# Board_Schamatic08.net
KiCad netlist of a schematic drawn in EAGLE
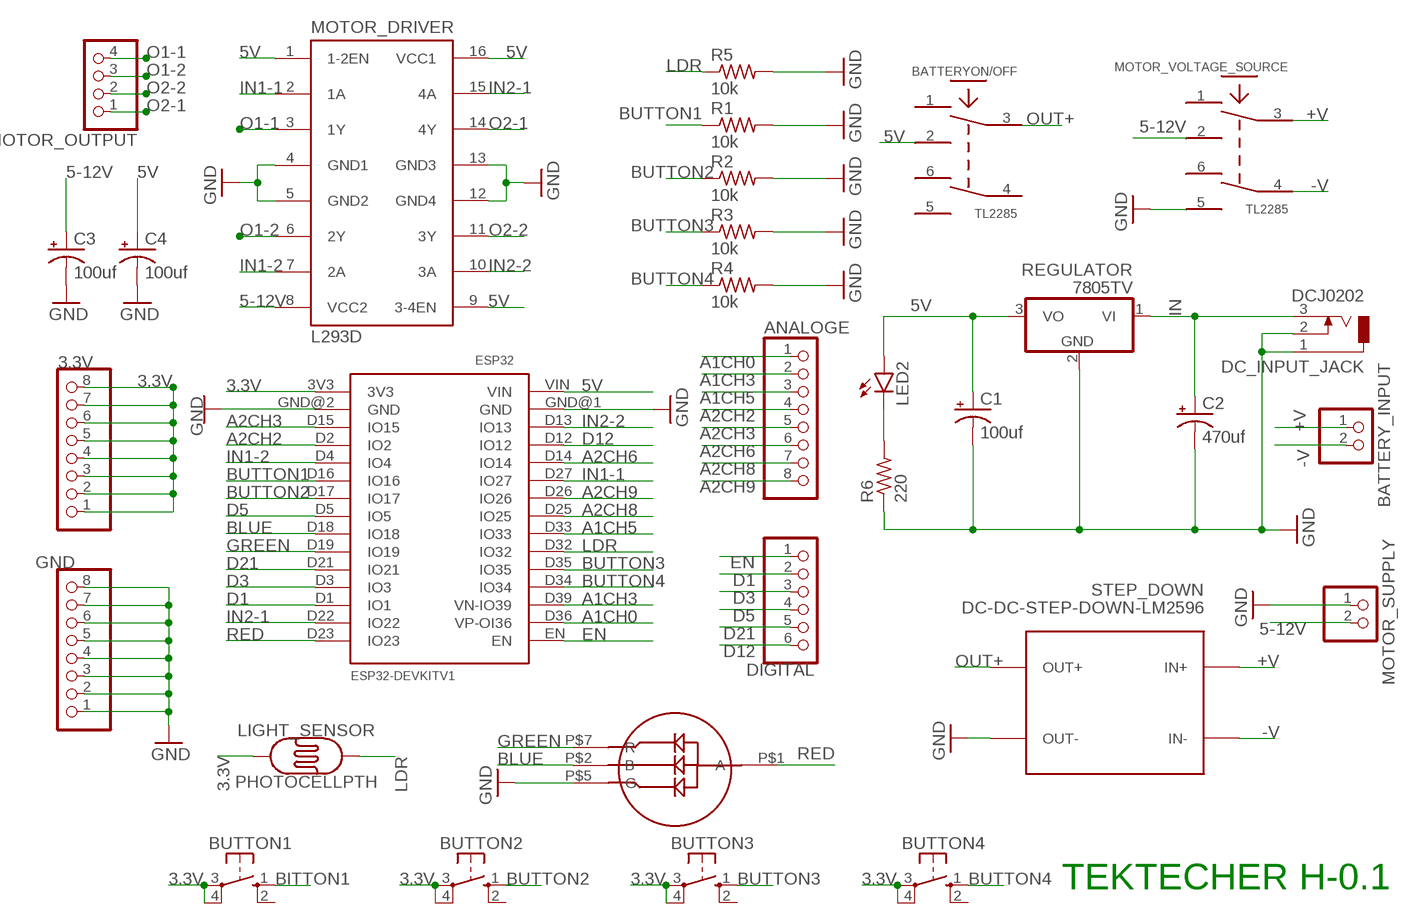
[diagram p0: schematic, sheet 1]

(export (version "E")
  (design (tool "Eeschema 10.0.6"))
  (components
    (comp (ref "3.3V")
      (value "PINHD-1X8")
      (footprint "eagle-import:1X08")
      (libsource (lib "eagle-import") (part "PINHD-1X8"))
    )
    (comp (ref "ANALOGE")
      (value "PINHD-1X8")
      (footprint "eagle-import:1X08")
      (libsource (lib "eagle-import") (part "PINHD-1X8"))
    )
    (comp (ref "BATTERYON/OFF")
      (value "TL2285")
      (footprint "eagle-import:TL2285_PCB")
      (libsource (lib "eagle-import") (part "TL2285"))
    )
    (comp (ref "BATTERY_INPUT")
      (value "PINHD-1X2")
      (footprint "eagle-import:1X02")
      (libsource (lib "eagle-import") (part "PINHD-1X2"))
    )
    (comp (ref "BUTTON1")
      (value "10-XX")
      (footprint "eagle-import:B3F-10XX")
      (fields (field (name "MPN") "B3F-1000"))
      (libsource (lib "eagle-import") (part "10-XX"))
    )
    (comp (ref "BUTTON2")
      (value "10-XX")
      (footprint "eagle-import:B3F-10XX")
      (fields (field (name "MPN") "B3F-1000"))
      (libsource (lib "eagle-import") (part "10-XX"))
    )
    (comp (ref "BUTTON3")
      (value "10-XX")
      (footprint "eagle-import:B3F-10XX")
      (fields (field (name "MPN") "B3F-1000"))
      (libsource (lib "eagle-import") (part "10-XX"))
    )
    (comp (ref "BUTTON4")
      (value "10-XX")
      (footprint "eagle-import:B3F-10XX")
      (fields (field (name "MPN") "B3F-1000"))
      (libsource (lib "eagle-import") (part "10-XX"))
    )
    (comp (ref "C1")
      (value "100uf")
      (footprint "eagle-import:E2-5")
      (libsource (lib "eagle-import") (part "CPOL-USE2-5"))
    )
    (comp (ref "C2")
      (value "470uf")
      (footprint "eagle-import:E2-5")
      (libsource (lib "eagle-import") (part "CPOL-USE2-5"))
    )
    (comp (ref "C3")
      (value "100uf")
      (footprint "eagle-import:E2-5")
      (libsource (lib "eagle-import") (part "CPOL-USE2-5"))
    )
    (comp (ref "C4")
      (value "100uf")
      (footprint "eagle-import:E2-5")
      (libsource (lib "eagle-import") (part "CPOL-USE2-5"))
    )
    (comp (ref "DC_INPUT_JACK")
      (value "DCJ0202")
      (footprint "eagle-import:DCJ0202")
      (libsource (lib "eagle-import") (part "DCJ0202"))
    )
    (comp (ref "DIGITAL")
      (value "PINHD-1X6")
      (footprint "eagle-import:1X06")
      (libsource (lib "eagle-import") (part "PINHD-1X6"))
    )
    (comp (ref "ESP32")
      (value "ESP32DEVKITV1")
      (footprint "eagle-import:ESP32-DEVKITV1")
      (libsource (lib "eagle-import") (part "ESP32DEVKITV1"))
    )
    (comp (ref "GND")
      (value "PINHD-1X8")
      (footprint "eagle-import:1X08")
      (libsource (lib "eagle-import") (part "PINHD-1X8"))
    )
    (comp (ref "LED2")
      (value "LED5MM")
      (footprint "eagle-import:LED5MM")
      (libsource (lib "eagle-import") (part "LED5MM"))
    )
    (comp (ref "LIGHT_SENSOR")
      (value "PHOTOCELLPTH")
      (footprint "eagle-import:PHOTOCELL")
      (libsource (lib "eagle-import") (part "PHOTOCELLPTH"))
    )
    (comp (ref "MOTOR_DRIVER")
      (value "L293D")
      (footprint "eagle-import:DIL16")
      (libsource (lib "eagle-import") (part "L293D"))
    )
    (comp (ref "MOTOR_OUTPUT")
      (value "PINHD-1X4")
      (footprint "eagle-import:1X04")
      (libsource (lib "eagle-import") (part "PINHD-1X4"))
    )
    (comp (ref "MOTOR_SUPPLY")
      (value "PINHD-1X2")
      (footprint "eagle-import:1X02")
      (libsource (lib "eagle-import") (part "PINHD-1X2"))
    )
    (comp (ref "MOTOR_VOLTAGE_SOURCE")
      (value "TL2285")
      (footprint "eagle-import:TL2285_PCB")
      (libsource (lib "eagle-import") (part "TL2285"))
    )
    (comp (ref "R1")
      (value "10k")
      (footprint "eagle-import:0207_10")
      (libsource (lib "eagle-import") (part "R-US_0207/10"))
    )
    (comp (ref "R2")
      (value "10k")
      (footprint "eagle-import:0207_10")
      (libsource (lib "eagle-import") (part "R-US_0207/10"))
    )
    (comp (ref "R3")
      (value "10k")
      (footprint "eagle-import:0207_10")
      (libsource (lib "eagle-import") (part "R-US_0207/10"))
    )
    (comp (ref "R4")
      (value "10k")
      (footprint "eagle-import:0207_10")
      (libsource (lib "eagle-import") (part "R-US_0207/10"))
    )
    (comp (ref "R5")
      (value "10k")
      (footprint "eagle-import:0207_10")
      (libsource (lib "eagle-import") (part "R-US_0207/10"))
    )
    (comp (ref "R6")
      (value "220")
      (footprint "eagle-import:0207_10")
      (libsource (lib "eagle-import") (part "R-US_0207/10"))
    )
    (comp (ref "REGULATOR")
      (value "7805TV")
      (footprint "eagle-import:TO220V")
      (libsource (lib "eagle-import") (part "78TV05"))
    )
    (comp (ref "RGB")
      (value "LED-4_PIN")
      (footprint "eagle-import:LED-4_PIN")
      (libsource (lib "eagle-import") (part "LED-4_PIN"))
    )
    (comp (ref "STEP_DOWN")
      (value "DC-DC-STEP-DOWN-LM2596")
      (footprint "eagle-import:DC-DC-STEP-DOWN-LM2596")
      (libsource (lib "eagle-import") (part "DC-DC-STEP-DOWN-LM2596"))
    )
  )
  (nets
    (net (code "1") (name "/+V") (class "Default")
      (node (ref "BATTERY_INPUT") (pin "1") (pinfunction "1_1") (pintype "passive"))
      (node (ref "MOTOR_VOLTAGE_SOURCE") (pin "3") (pinfunction "P3_3") (pintype "bidirectional"))
      (node (ref "STEP_DOWN") (pin "IN+") (pinfunction "IN+_IN+") (pintype "bidirectional"))
    )
    (net (code "2") (name "/-V") (class "Default")
      (node (ref "BATTERY_INPUT") (pin "2") (pinfunction "2_2") (pintype "passive"))
      (node (ref "MOTOR_VOLTAGE_SOURCE") (pin "4") (pinfunction "P4_4") (pintype "bidirectional"))
      (node (ref "STEP_DOWN") (pin "IN-") (pinfunction "IN-_IN-") (pintype "bidirectional"))
    )
    (net (code "3") (name "/3.3V") (class "Default")
      (node (ref "3.3V") (pin "1") (pinfunction "1_1") (pintype "passive"))
      (node (ref "3.3V") (pin "2") (pinfunction "2_2") (pintype "passive"))
      (node (ref "3.3V") (pin "3") (pinfunction "3_3") (pintype "passive"))
      (node (ref "3.3V") (pin "4") (pinfunction "4_4") (pintype "passive"))
      (node (ref "3.3V") (pin "5") (pinfunction "5_5") (pintype "passive"))
      (node (ref "3.3V") (pin "6") (pinfunction "6_6") (pintype "passive"))
      (node (ref "3.3V") (pin "7") (pinfunction "7_7") (pintype "passive"))
      (node (ref "3.3V") (pin "8") (pinfunction "8_8") (pintype "passive"))
      (node (ref "BUTTON1") (pin "3") (pinfunction "P_3") (pintype "passive"))
      (node (ref "BUTTON1") (pin "4") (pinfunction "P1_4") (pintype "passive"))
      (node (ref "BUTTON2") (pin "3") (pinfunction "P_3") (pintype "passive"))
      (node (ref "BUTTON2") (pin "4") (pinfunction "P1_4") (pintype "passive"))
      (node (ref "BUTTON3") (pin "3") (pinfunction "P_3") (pintype "passive"))
      (node (ref "BUTTON3") (pin "4") (pinfunction "P1_4") (pintype "passive"))
      (node (ref "BUTTON4") (pin "3") (pinfunction "P_3") (pintype "passive"))
      (node (ref "BUTTON4") (pin "4") (pinfunction "P1_4") (pintype "passive"))
      (node (ref "ESP32") (pin "3V3") (pinfunction "3V3_3V3") (pintype "bidirectional"))
      (node (ref "LIGHT_SENSOR") (pin "1") (pinfunction "P$1_1") (pintype "bidirectional"))
    )
    (net (code "4") (name "/5-12V") (class "Default")
      (node (ref "C3") (pin "+") (pinfunction "+_+") (pintype "passive"))
      (node (ref "MOTOR_DRIVER") (pin "8") (pinfunction "VCC2_8") (pintype "power_in"))
      (node (ref "MOTOR_SUPPLY") (pin "2") (pinfunction "2_2") (pintype "passive"))
      (node (ref "MOTOR_VOLTAGE_SOURCE") (pin "2") (pinfunction "P2_2") (pintype "bidirectional"))
    )
    (net (code "5") (name "/5V") (class "Default")
      (node (ref "BATTERYON/OFF") (pin "2") (pinfunction "P2_2") (pintype "bidirectional"))
      (node (ref "C1") (pin "+") (pinfunction "+_+") (pintype "passive"))
      (node (ref "C4") (pin "+") (pinfunction "+_+") (pintype "passive"))
      (node (ref "ESP32") (pin "VIN") (pinfunction "VIN_VIN") (pintype "bidirectional"))
      (node (ref "LED2") (pin "A") (pinfunction "A_A") (pintype "passive"))
      (node (ref "MOTOR_DRIVER") (pin "1") (pinfunction "1-2EN_1") (pintype "input"))
      (node (ref "MOTOR_DRIVER") (pin "16") (pinfunction "VCC1_16") (pintype "power_in"))
      (node (ref "MOTOR_DRIVER") (pin "9") (pinfunction "3-4EN_9") (pintype "input"))
      (node (ref "REGULATOR") (pin "3") (pinfunction "VO_3") (pintype "passive"))
    )
    (net (code "6") (name "/A1CH0") (class "Default")
      (node (ref "ANALOGE") (pin "1") (pinfunction "1_1") (pintype "passive"))
      (node (ref "ESP32") (pin "D36") (pinfunction "VP-OI36_D36") (pintype "bidirectional"))
    )
    (net (code "7") (name "/A1CH3") (class "Default")
      (node (ref "ANALOGE") (pin "2") (pinfunction "2_2") (pintype "passive"))
      (node (ref "ESP32") (pin "D39") (pinfunction "VN-IO39_D39") (pintype "bidirectional"))
    )
    (net (code "8") (name "/A1CH5") (class "Default")
      (node (ref "ANALOGE") (pin "3") (pinfunction "3_3") (pintype "passive"))
      (node (ref "ESP32") (pin "D33") (pinfunction "IO33_D33") (pintype "bidirectional"))
    )
    (net (code "9") (name "/A2CH2") (class "Default")
      (node (ref "ANALOGE") (pin "4") (pinfunction "4_4") (pintype "passive"))
      (node (ref "ESP32") (pin "D2") (pinfunction "IO2_D2") (pintype "bidirectional"))
    )
    (net (code "10") (name "/A2CH3") (class "Default")
      (node (ref "ANALOGE") (pin "5") (pinfunction "5_5") (pintype "passive"))
      (node (ref "ESP32") (pin "D15") (pinfunction "IO15_D15") (pintype "bidirectional"))
    )
    (net (code "11") (name "/A2CH6") (class "Default")
      (node (ref "ANALOGE") (pin "6") (pinfunction "6_6") (pintype "passive"))
      (node (ref "ESP32") (pin "D14") (pinfunction "IO14_D14") (pintype "bidirectional"))
    )
    (net (code "12") (name "/A2CH8") (class "Default")
      (node (ref "ANALOGE") (pin "7") (pinfunction "7_7") (pintype "passive"))
      (node (ref "ESP32") (pin "D25") (pinfunction "IO25_D25") (pintype "bidirectional"))
    )
    (net (code "13") (name "/A2CH9") (class "Default")
      (node (ref "ANALOGE") (pin "8") (pinfunction "8_8") (pintype "passive"))
      (node (ref "ESP32") (pin "D26") (pinfunction "IO26_D26") (pintype "bidirectional"))
    )
    (net (code "14") (name "/BITTON1") (class "Default")
      (node (ref "BUTTON1") (pin "1") (pinfunction "S_1") (pintype "passive"))
    )
    (net (code "15") (name "/BLUE") (class "Default")
      (node (ref "ESP32") (pin "D18") (pinfunction "IO18_D18") (pintype "bidirectional"))
      (node (ref "RGB") (pin "P$2") (pinfunction "B_P$2") (pintype "bidirectional"))
    )
    (net (code "16") (name "/BUTTON1") (class "Default")
      (node (ref "ESP32") (pin "D16") (pinfunction "IO16_D16") (pintype "bidirectional"))
      (node (ref "R1") (pin "1") (pinfunction "1_1") (pintype "passive"))
    )
    (net (code "17") (name "/BUTTON2") (class "Default")
      (node (ref "BUTTON2") (pin "1") (pinfunction "S_1") (pintype "passive"))
      (node (ref "ESP32") (pin "D17") (pinfunction "IO17_D17") (pintype "bidirectional"))
      (node (ref "R2") (pin "1") (pinfunction "1_1") (pintype "passive"))
    )
    (net (code "18") (name "/BUTTON3") (class "Default")
      (node (ref "BUTTON3") (pin "1") (pinfunction "S_1") (pintype "passive"))
      (node (ref "ESP32") (pin "D35") (pinfunction "IO35_D35") (pintype "bidirectional"))
      (node (ref "R3") (pin "1") (pinfunction "1_1") (pintype "passive"))
    )
    (net (code "19") (name "/BUTTON4") (class "Default")
      (node (ref "BUTTON4") (pin "1") (pinfunction "S_1") (pintype "passive"))
      (node (ref "ESP32") (pin "D34") (pinfunction "IO34_D34") (pintype "bidirectional"))
      (node (ref "R4") (pin "1") (pinfunction "1_1") (pintype "passive"))
    )
    (net (code "20") (name "/D1") (class "Default")
      (node (ref "DIGITAL") (pin "2") (pinfunction "2_2") (pintype "passive"))
      (node (ref "ESP32") (pin "D1") (pinfunction "IO1_D1") (pintype "bidirectional"))
    )
    (net (code "21") (name "/D3") (class "Default")
      (node (ref "DIGITAL") (pin "3") (pinfunction "3_3") (pintype "passive"))
      (node (ref "ESP32") (pin "D3") (pinfunction "IO3_D3") (pintype "bidirectional"))
    )
    (net (code "22") (name "/D5") (class "Default")
      (node (ref "DIGITAL") (pin "4") (pinfunction "4_4") (pintype "passive"))
      (node (ref "ESP32") (pin "D5") (pinfunction "IO5_D5") (pintype "bidirectional"))
    )
    (net (code "23") (name "/D12") (class "Default")
      (node (ref "DIGITAL") (pin "6") (pinfunction "6_6") (pintype "passive"))
      (node (ref "ESP32") (pin "D12") (pinfunction "IO12_D12") (pintype "bidirectional"))
    )
    (net (code "24") (name "/D21") (class "Default")
      (node (ref "DIGITAL") (pin "5") (pinfunction "5_5") (pintype "passive"))
      (node (ref "ESP32") (pin "D21") (pinfunction "IO21_D21") (pintype "bidirectional"))
    )
    (net (code "25") (name "/EN") (class "Default")
      (node (ref "DIGITAL") (pin "1") (pinfunction "1_1") (pintype "passive"))
      (node (ref "ESP32") (pin "EN") (pinfunction "EN_EN") (pintype "bidirectional"))
    )
    (net (code "26") (name "/GREEN") (class "Default")
      (node (ref "ESP32") (pin "D19") (pinfunction "IO19_D19") (pintype "bidirectional"))
      (node (ref "RGB") (pin "P$7") (pinfunction "R_P$7") (pintype "bidirectional"))
    )
    (net (code "27") (name "/IN") (class "Default")
      (node (ref "C2") (pin "+") (pinfunction "+_+") (pintype "passive"))
      (node (ref "DC_INPUT_JACK") (pin "3") (pinfunction "3_3") (pintype "passive"))
      (node (ref "REGULATOR") (pin "1") (pinfunction "VI_1") (pintype "input"))
    )
    (net (code "28") (name "/IN1-1") (class "Default")
      (node (ref "ESP32") (pin "D27") (pinfunction "IO27_D27") (pintype "bidirectional"))
      (node (ref "MOTOR_DRIVER") (pin "2") (pinfunction "1A_2") (pintype "input"))
    )
    (net (code "29") (name "/IN1-2") (class "Default")
      (node (ref "ESP32") (pin "D4") (pinfunction "IO4_D4") (pintype "bidirectional"))
      (node (ref "MOTOR_DRIVER") (pin "7") (pinfunction "2A_7") (pintype "input"))
    )
    (net (code "30") (name "/IN2-1") (class "Default")
      (node (ref "ESP32") (pin "D22") (pinfunction "IO22_D22") (pintype "bidirectional"))
      (node (ref "MOTOR_DRIVER") (pin "15") (pinfunction "4A_15") (pintype "input"))
    )
    (net (code "31") (name "/IN2-2") (class "Default")
      (node (ref "ESP32") (pin "D13") (pinfunction "IO13_D13") (pintype "bidirectional"))
      (node (ref "MOTOR_DRIVER") (pin "10") (pinfunction "3A_10") (pintype "input"))
    )
    (net (code "32") (name "/LDR") (class "Default")
      (node (ref "ESP32") (pin "D32") (pinfunction "IO32_D32") (pintype "bidirectional"))
      (node (ref "LIGHT_SENSOR") (pin "2") (pinfunction "P$2_2") (pintype "bidirectional"))
      (node (ref "R5") (pin "1") (pinfunction "1_1") (pintype "passive"))
    )
    (net (code "33") (name "/O1-1") (class "Default")
      (node (ref "MOTOR_DRIVER") (pin "3") (pinfunction "1Y_3") (pintype "output"))
      (node (ref "MOTOR_OUTPUT") (pin "4") (pinfunction "4_4") (pintype "passive"))
    )
    (net (code "34") (name "/O1-2") (class "Default")
      (node (ref "MOTOR_DRIVER") (pin "6") (pinfunction "2Y_6") (pintype "output"))
      (node (ref "MOTOR_OUTPUT") (pin "3") (pinfunction "3_3") (pintype "passive"))
    )
    (net (code "35") (name "/O2-1") (class "Default")
      (node (ref "MOTOR_DRIVER") (pin "14") (pinfunction "4Y_14") (pintype "output"))
      (node (ref "MOTOR_OUTPUT") (pin "1") (pinfunction "1_1") (pintype "passive"))
    )
    (net (code "36") (name "/O2-2") (class "Default")
      (node (ref "MOTOR_DRIVER") (pin "11") (pinfunction "3Y_11") (pintype "output"))
      (node (ref "MOTOR_OUTPUT") (pin "2") (pinfunction "2_2") (pintype "passive"))
    )
    (net (code "37") (name "/OUT+") (class "Default")
      (node (ref "BATTERYON/OFF") (pin "3") (pinfunction "P3_3") (pintype "bidirectional"))
      (node (ref "STEP_DOWN") (pin "OUT+") (pinfunction "OUT+_OUT+") (pintype "bidirectional"))
    )
    (net (code "38") (name "/RED") (class "Default")
      (node (ref "ESP32") (pin "D23") (pinfunction "IO23_D23") (pintype "bidirectional"))
      (node (ref "RGB") (pin "P$1") (pinfunction "A_P$1") (pintype "bidirectional"))
    )
    (net (code "39") (name "GND") (class "Default")
      (node (ref "C1") (pin "-") (pinfunction "-_-") (pintype "passive"))
      (node (ref "C2") (pin "-") (pinfunction "-_-") (pintype "passive"))
      (node (ref "C3") (pin "-") (pinfunction "-_-") (pintype "passive"))
      (node (ref "C4") (pin "-") (pinfunction "-_-") (pintype "passive"))
      (node (ref "DC_INPUT_JACK") (pin "1") (pinfunction "1_1") (pintype "passive"))
      (node (ref "DC_INPUT_JACK") (pin "2") (pinfunction "2_2") (pintype "passive"))
      (node (ref "ESP32") (pin "GND@1") (pinfunction "GND_GND@1") (pintype "bidirectional"))
      (node (ref "ESP32") (pin "GND@2") (pinfunction "GND_GND@2") (pintype "bidirectional"))
      (node (ref "GND") (pin "1") (pinfunction "1_1") (pintype "passive"))
      (node (ref "GND") (pin "2") (pinfunction "2_2") (pintype "passive"))
      (node (ref "GND") (pin "3") (pinfunction "3_3") (pintype "passive"))
      (node (ref "GND") (pin "4") (pinfunction "4_4") (pintype "passive"))
      (node (ref "GND") (pin "5") (pinfunction "5_5") (pintype "passive"))
      (node (ref "GND") (pin "6") (pinfunction "6_6") (pintype "passive"))
      (node (ref "GND") (pin "7") (pinfunction "7_7") (pintype "passive"))
      (node (ref "GND") (pin "8") (pinfunction "8_8") (pintype "passive"))
      (node (ref "MOTOR_DRIVER") (pin "12") (pinfunction "GND4_12") (pintype "power_in"))
      (node (ref "MOTOR_DRIVER") (pin "13") (pinfunction "GND3_13") (pintype "power_in"))
      (node (ref "MOTOR_DRIVER") (pin "4") (pinfunction "GND1_4") (pintype "power_in"))
      (node (ref "MOTOR_DRIVER") (pin "5") (pinfunction "GND2_5") (pintype "power_in"))
      (node (ref "MOTOR_SUPPLY") (pin "1") (pinfunction "1_1") (pintype "passive"))
      (node (ref "MOTOR_VOLTAGE_SOURCE") (pin "5") (pinfunction "P5_5") (pintype "bidirectional"))
      (node (ref "R1") (pin "2") (pinfunction "2_2") (pintype "passive"))
      (node (ref "R2") (pin "2") (pinfunction "2_2") (pintype "passive"))
      (node (ref "R3") (pin "2") (pinfunction "2_2") (pintype "passive"))
      (node (ref "R4") (pin "2") (pinfunction "2_2") (pintype "passive"))
      (node (ref "R5") (pin "2") (pinfunction "2_2") (pintype "passive"))
      (node (ref "R6") (pin "1") (pinfunction "1_1") (pintype "passive"))
      (node (ref "REGULATOR") (pin "2") (pinfunction "GND_2") (pintype "passive"))
      (node (ref "RGB") (pin "P$5") (pinfunction "G_P$5") (pintype "bidirectional"))
      (node (ref "STEP_DOWN") (pin "OUT-") (pinfunction "OUT-_OUT-") (pintype "bidirectional"))
    )
    (net (code "40") (name "Net-(LED2-C)") (class "Default")
      (node (ref "LED2") (pin "K") (pinfunction "C_K") (pintype "passive"))
      (node (ref "R6") (pin "2") (pinfunction "2_2") (pintype "passive"))
    )
    (net (code "41") (name "unconnected-(BATTERYON/OFF-P1-Pad1)") (class "Default")
      (node (ref "BATTERYON/OFF") (pin "1") (pinfunction "P1_1") (pintype "bidirectional"))
    )
    (net (code "42") (name "unconnected-(BATTERYON/OFF-P4-Pad4)") (class "Default")
      (node (ref "BATTERYON/OFF") (pin "4") (pinfunction "P4_4") (pintype "bidirectional"))
    )
    (net (code "43") (name "unconnected-(BATTERYON/OFF-P5-Pad5)") (class "Default")
      (node (ref "BATTERYON/OFF") (pin "5") (pinfunction "P5_5") (pintype "bidirectional"))
    )
    (net (code "44") (name "unconnected-(BATTERYON/OFF-P6-Pad6)") (class "Default")
      (node (ref "BATTERYON/OFF") (pin "6") (pinfunction "P6_6") (pintype "bidirectional"))
    )
    (net (code "45") (name "unconnected-(BUTTON1-S1-Pad2)") (class "Default")
      (node (ref "BUTTON1") (pin "2") (pinfunction "S1_2") (pintype "passive"))
    )
    (net (code "46") (name "unconnected-(BUTTON2-S1-Pad2)") (class "Default")
      (node (ref "BUTTON2") (pin "2") (pinfunction "S1_2") (pintype "passive"))
    )
    (net (code "47") (name "unconnected-(BUTTON3-S1-Pad2)") (class "Default")
      (node (ref "BUTTON3") (pin "2") (pinfunction "S1_2") (pintype "passive"))
    )
    (net (code "48") (name "unconnected-(BUTTON4-S1-Pad2)") (class "Default")
      (node (ref "BUTTON4") (pin "2") (pinfunction "S1_2") (pintype "passive"))
    )
    (net (code "49") (name "unconnected-(MOTOR_VOLTAGE_SOURCE-P1-Pad1)") (class "Default")
      (node (ref "MOTOR_VOLTAGE_SOURCE") (pin "1") (pinfunction "P1_1") (pintype "bidirectional"))
    )
    (net (code "50") (name "unconnected-(MOTOR_VOLTAGE_SOURCE-P6-Pad6)") (class "Default")
      (node (ref "MOTOR_VOLTAGE_SOURCE") (pin "6") (pinfunction "P6_6") (pintype "bidirectional"))
    )
  )
)
